# RMS.net
KiCad netlist of a schematic drawn in Altium Designer
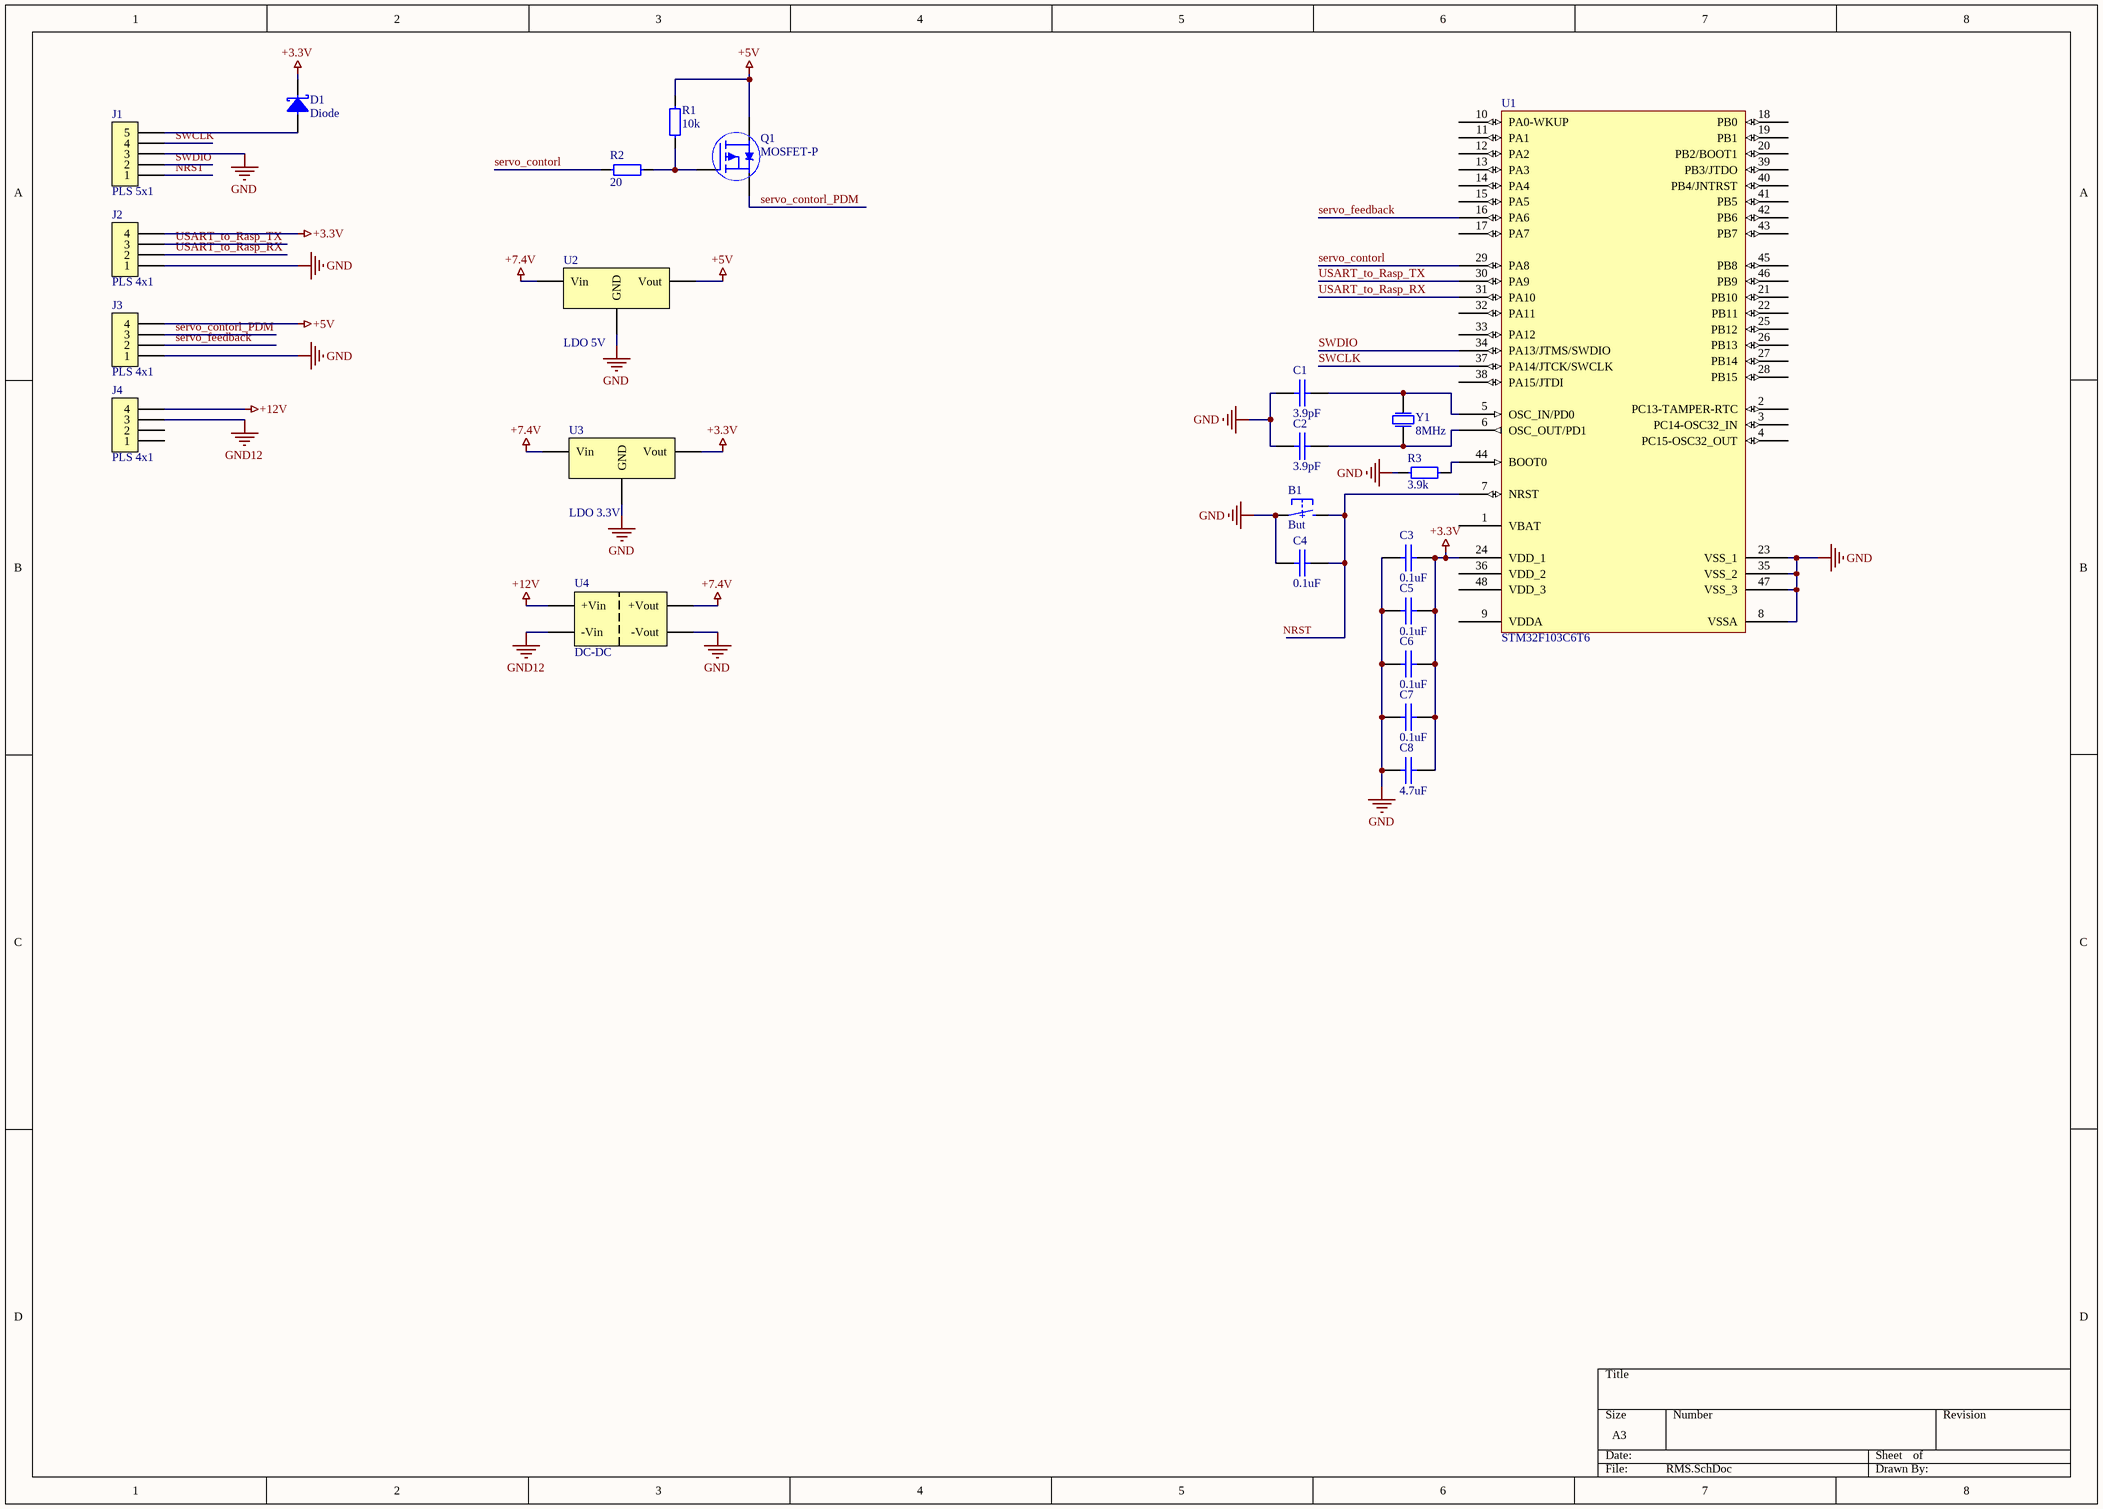
[diagram p0: RMS.SchDoc]

(export (version "E")
  (design (tool "Eeschema 10.0.6"))
  (components
    (comp (ref "B1")
      (value "But")
      (footprint "BUTTON 6x3.5")
      (description "Button 2 Conn SMD")
      (libsource (lib "RoboCor") (part "Button"))
    )
    (comp (ref "C1")
      (value "3.9pF")
      (footprint "0805 Capicator")
      (libsource (lib "RoboCor") (part "Cap 39pF"))
    )
    (comp (ref "C2")
      (value "3.9pF")
      (footprint "0805 Capicator")
      (libsource (lib "RoboCor") (part "Cap 39pF"))
    )
    (comp (ref "C3")
      (value "0.1uF")
      (footprint "0805 Capicator")
      (libsource (lib "RoboCor") (part "Cap 0.1uF"))
    )
    (comp (ref "C4")
      (value "0.1uF")
      (footprint "0805 Capicator")
      (libsource (lib "RoboCor") (part "Cap 0.1uF"))
    )
    (comp (ref "C5")
      (value "0.1uF")
      (footprint "0805 Capicator")
      (libsource (lib "RoboCor") (part "Cap 0.1uF"))
    )
    (comp (ref "C6")
      (value "0.1uF")
      (footprint "0805 Capicator")
      (libsource (lib "RoboCor") (part "Cap 0.1uF"))
    )
    (comp (ref "C7")
      (value "0.1uF")
      (footprint "0805 Capicator")
      (libsource (lib "RoboCor") (part "Cap 0.1uF"))
    )
    (comp (ref "C8")
      (value "4.7uF")
      (footprint "0805 Capicator")
      (libsource (lib "RoboCor") (part "Cap 4.7uF"))
    )
    (comp (ref "D1")
      (value "Diode")
      (footprint "sod-123")
      (description "0.5 A, Low Forward Voltage less than 385 mV, 400 mW Power Dissipation Package")
      (libsource (lib "RoboCor") (part "Diode Schottky"))
    )
    (comp (ref "J1")
      (value "PLS 5x1")
      (footprint "PLS 5x1")
      (description "Header, 5-Pin")
      (libsource (lib "RoboCor") (part "Conn 5"))
    )
    (comp (ref "J2")
      (value "PLS 4x1")
      (footprint "PLS 4x1")
      (description "Header, 4-Pin")
      (libsource (lib "RoboCor") (part "Conn 4"))
    )
    (comp (ref "J3")
      (value "PLS 4x1")
      (footprint "PLS 4x1")
      (description "Header, 4-Pin")
      (libsource (lib "RoboCor") (part "Conn 4"))
    )
    (comp (ref "J4")
      (value "PLS 4x1")
      (footprint "PLS 4x1")
      (description "Header, 4-Pin")
      (libsource (lib "RoboCor") (part "Conn 4"))
    )
    (comp (ref "Q1")
      (value "MOSFET-P")
      (footprint "SOT-23")
      (description "P-Channel Power MOSFET 12V to 20V, Infineon")
      (libsource (lib "RoboCor") (part "MOSFET-P"))
    )
    (comp (ref "R1") (value "10k") (footprint "0805 Resistor") (libsource (lib "RoboCor") (part "Res 10k")))
    (comp (ref "R2") (value "20") (footprint "0805 Resistor") (libsource (lib "RoboCor") (part "Res 20")))
    (comp (ref "R3") (value "3.9k") (footprint "0805 Resistor") (libsource (lib "RoboCor") (part "Res 3.9k")))
    (comp (ref "U1")
      (value "STM32F103C6T6")
      (footprint "STM32F103C6T6")
      (libsource (lib "RoboCor") (part "STM32F103C6T6"))
    )
    (comp (ref "U2")
      (value "LDO 5V")
      (footprint "TO-252")
      (description "LDO Regulator Pos 5V 1A")
      (libsource (lib "RoboCor") (part "LDO 5V"))
    )
    (comp (ref "U3")
      (value "LDO 3.3V")
      (footprint "SOT-223")
      (description "LDO Regulator Pos 3.3V 1.3A 4-Pin(3+Tab) SOT-223 T/R")
      (libsource (lib "RoboCor") (part "LDO 3.3V"))
    )
    (comp (ref "U4") (value "DC-DC") (footprint "DC-DC") (libsource (lib "RoboCor") (part "DC-DC")))
    (comp (ref "Y1")
      (value "8MHz")
      (footprint "hc-49sm")
      (description "Crystal. HC-49SM (US)")
      (libsource (lib "RoboCor") (part "Crystal 8MHz"))
    )
  )
  (nets
    (net (code "1") (name "+3.3V") (class "Default")
      (node (ref "C3") (pin "2") (pinfunction "2_2") (pintype "passive"))
      (node (ref "C5") (pin "2") (pinfunction "2_2") (pintype "passive"))
      (node (ref "C6") (pin "2") (pinfunction "2_2") (pintype "passive"))
      (node (ref "C7") (pin "2") (pinfunction "2_2") (pintype "passive"))
      (node (ref "C8") (pin "2") (pinfunction "2_2") (pintype "passive"))
      (node (ref "D1") (pin "2") (pinfunction "2_2") (pintype "passive"))
      (node (ref "J2") (pin "4") (pinfunction "4_4") (pintype "passive"))
      (node (ref "U1") (pin "24") (pinfunction "VDD_1_24") (pintype "power_in"))
      (node (ref "U3") (pin "2") (pinfunction "Vout_2") (pintype "power_in"))
    )
    (net (code "2") (name "+5V") (class "Default")
      (node (ref "J3") (pin "4") (pinfunction "4_4") (pintype "passive"))
      (node (ref "Q1") (pin "3") (pinfunction "Drain_3") (pintype "passive"))
      (node (ref "R1") (pin "2") (pinfunction "2_2") (pintype "passive"))
      (node (ref "U2") (pin "2") (pinfunction "Vout_2") (pintype "power_in"))
    )
    (net (code "3") (name "+7.4V") (class "Default")
      (node (ref "U2") (pin "3") (pinfunction "Vin_3") (pintype "power_in"))
      (node (ref "U3") (pin "3") (pinfunction "Vin_3") (pintype "power_in"))
      (node (ref "U4") (pin "3") (pinfunction "+Vout_3") (pintype "power_in"))
    )
    (net (code "4") (name "+12V") (class "Default")
      (node (ref "J4") (pin "4") (pinfunction "4_4") (pintype "passive"))
      (node (ref "U4") (pin "1") (pinfunction "+Vin_1") (pintype "power_in"))
    )
    (net (code "5") (name "/NRST") (class "Default")
      (node (ref "B1") (pin "2") (pinfunction "2_2") (pintype "passive"))
      (node (ref "C4") (pin "2") (pinfunction "2_2") (pintype "passive"))
      (node (ref "J1") (pin "1") (pinfunction "1_1") (pintype "passive"))
      (node (ref "U1") (pin "7") (pinfunction "NRST_7") (pintype "bidirectional"))
    )
    (net (code "6") (name "/SWCLK") (class "Default")
      (node (ref "J1") (pin "4") (pinfunction "4_4") (pintype "passive"))
      (node (ref "U1") (pin "37") (pinfunction "PA14/JTCK/SWCLK_37") (pintype "bidirectional"))
    )
    (net (code "7") (name "/SWDIO") (class "Default")
      (node (ref "J1") (pin "2") (pinfunction "2_2") (pintype "passive"))
      (node (ref "U1") (pin "34") (pinfunction "PA13/JTMS/SWDIO_34") (pintype "bidirectional"))
    )
    (net (code "8") (name "/USART_to_Rasp_RX") (class "Default")
      (node (ref "J2") (pin "2") (pinfunction "2_2") (pintype "passive"))
      (node (ref "U1") (pin "31") (pinfunction "PA10_31") (pintype "bidirectional"))
    )
    (net (code "9") (name "/USART_to_Rasp_TX") (class "Default")
      (node (ref "J2") (pin "3") (pinfunction "3_3") (pintype "passive"))
      (node (ref "U1") (pin "30") (pinfunction "PA9_30") (pintype "bidirectional"))
    )
    (net (code "10") (name "/servo_contorl") (class "Default")
      (node (ref "R2") (pin "1") (pinfunction "1_1") (pintype "passive"))
      (node (ref "U1") (pin "29") (pinfunction "PA8_29") (pintype "bidirectional"))
    )
    (net (code "11") (name "/servo_contorl_PDM") (class "Default")
      (node (ref "J3") (pin "3") (pinfunction "3_3") (pintype "passive"))
      (node (ref "Q1") (pin "2") (pinfunction "Source_2") (pintype "passive"))
    )
    (net (code "12") (name "/servo_feedback") (class "Default")
      (node (ref "J3") (pin "2") (pinfunction "2_2") (pintype "passive"))
      (node (ref "U1") (pin "16") (pinfunction "PA6_16") (pintype "bidirectional"))
    )
    (net (code "13") (name "GND") (class "Default")
      (node (ref "B1") (pin "1") (pinfunction "1_1") (pintype "passive"))
      (node (ref "C1") (pin "1") (pinfunction "1_1") (pintype "passive"))
      (node (ref "C2") (pin "1") (pinfunction "1_1") (pintype "passive"))
      (node (ref "C3") (pin "1") (pinfunction "1_1") (pintype "passive"))
      (node (ref "C4") (pin "1") (pinfunction "1_1") (pintype "passive"))
      (node (ref "C5") (pin "1") (pinfunction "1_1") (pintype "passive"))
      (node (ref "C6") (pin "1") (pinfunction "1_1") (pintype "passive"))
      (node (ref "C7") (pin "1") (pinfunction "1_1") (pintype "passive"))
      (node (ref "C8") (pin "1") (pinfunction "1_1") (pintype "passive"))
      (node (ref "J1") (pin "3") (pinfunction "3_3") (pintype "passive"))
      (node (ref "J2") (pin "1") (pinfunction "1_1") (pintype "passive"))
      (node (ref "J3") (pin "1") (pinfunction "1_1") (pintype "passive"))
      (node (ref "R3") (pin "1") (pinfunction "1_1") (pintype "passive"))
      (node (ref "U1") (pin "23") (pinfunction "VSS_1_23") (pintype "power_in"))
      (node (ref "U1") (pin "35") (pinfunction "VSS_2_35") (pintype "power_in"))
      (node (ref "U1") (pin "47") (pinfunction "VSS_3_47") (pintype "power_in"))
      (node (ref "U1") (pin "8") (pinfunction "VSSA_8") (pintype "power_in"))
      (node (ref "U2") (pin "1") (pinfunction "GND_1") (pintype "power_in"))
      (node (ref "U3") (pin "1") (pinfunction "GND_1") (pintype "power_in"))
      (node (ref "U4") (pin "4") (pinfunction "-Vout_4") (pintype "power_in"))
    )
    (net (code "14") (name "GND12") (class "Default")
      (node (ref "J4") (pin "3") (pinfunction "3_3") (pintype "passive"))
      (node (ref "U4") (pin "2") (pinfunction "-Vin_2") (pintype "power_in"))
    )
    (net (code "15") (name "Net-(D1-Pad1)") (class "Default")
      (node (ref "D1") (pin "1") (pinfunction "1_1") (pintype "passive"))
      (node (ref "J1") (pin "5") (pinfunction "5_5") (pintype "passive"))
    )
    (net (code "16") (name "Net-(Q1-Gate)") (class "Default")
      (node (ref "Q1") (pin "1") (pinfunction "Gate_1") (pintype "passive"))
      (node (ref "R1") (pin "1") (pinfunction "1_1") (pintype "passive"))
      (node (ref "R2") (pin "2") (pinfunction "2_2") (pintype "passive"))
    )
    (net (code "17") (name "Net-(U1-BOOT0)") (class "Default")
      (node (ref "R3") (pin "2") (pinfunction "2_2") (pintype "passive"))
      (node (ref "U1") (pin "44") (pinfunction "BOOT0_44") (pintype "input"))
    )
    (net (code "18") (name "Net-(U1-OSC_IN{slash}PD0)") (class "Default")
      (node (ref "C1") (pin "2") (pinfunction "2_2") (pintype "passive"))
      (node (ref "U1") (pin "5") (pinfunction "OSC_IN/PD0_5") (pintype "input"))
      (node (ref "Y1") (pin "2") (pinfunction "2_2") (pintype "passive"))
    )
    (net (code "19") (name "Net-(U1-OSC_OUT{slash}PD1)") (class "Default")
      (node (ref "C2") (pin "2") (pinfunction "2_2") (pintype "passive"))
      (node (ref "U1") (pin "6") (pinfunction "OSC_OUT/PD1_6") (pintype "output"))
      (node (ref "Y1") (pin "1") (pinfunction "1_1") (pintype "passive"))
    )
    (net (code "20") (name "unconnected-(J4-Pad1)") (class "Default")
      (node (ref "J4") (pin "1") (pinfunction "1_1") (pintype "passive"))
    )
    (net (code "21") (name "unconnected-(J4-Pad2)") (class "Default")
      (node (ref "J4") (pin "2") (pinfunction "2_2") (pintype "passive"))
    )
    (net (code "22") (name "unconnected-(U1-PA0-WKUP-Pad10)") (class "Default")
      (node (ref "U1") (pin "10") (pinfunction "PA0-WKUP_10") (pintype "bidirectional"))
    )
    (net (code "23") (name "unconnected-(U1-PA1-Pad11)") (class "Default")
      (node (ref "U1") (pin "11") (pinfunction "PA1_11") (pintype "bidirectional"))
    )
    (net (code "24") (name "unconnected-(U1-PA2-Pad12)") (class "Default")
      (node (ref "U1") (pin "12") (pinfunction "PA2_12") (pintype "bidirectional"))
    )
    (net (code "25") (name "unconnected-(U1-PA3-Pad13)") (class "Default")
      (node (ref "U1") (pin "13") (pinfunction "PA3_13") (pintype "bidirectional"))
    )
    (net (code "26") (name "unconnected-(U1-PA4-Pad14)") (class "Default")
      (node (ref "U1") (pin "14") (pinfunction "PA4_14") (pintype "bidirectional"))
    )
    (net (code "27") (name "unconnected-(U1-PA5-Pad15)") (class "Default")
      (node (ref "U1") (pin "15") (pinfunction "PA5_15") (pintype "bidirectional"))
    )
    (net (code "28") (name "unconnected-(U1-PA7-Pad17)") (class "Default")
      (node (ref "U1") (pin "17") (pinfunction "PA7_17") (pintype "bidirectional"))
    )
    (net (code "29") (name "unconnected-(U1-PA11-Pad32)") (class "Default")
      (node (ref "U1") (pin "32") (pinfunction "PA11_32") (pintype "bidirectional"))
    )
    (net (code "30") (name "unconnected-(U1-PA12-Pad33)") (class "Default")
      (node (ref "U1") (pin "33") (pinfunction "PA12_33") (pintype "bidirectional"))
    )
    (net (code "31") (name "unconnected-(U1-PA15{slash}JTDI-Pad38)") (class "Default")
      (node (ref "U1") (pin "38") (pinfunction "PA15/JTDI_38") (pintype "bidirectional"))
    )
    (net (code "32") (name "unconnected-(U1-PB0-Pad18)") (class "Default")
      (node (ref "U1") (pin "18") (pinfunction "PB0_18") (pintype "bidirectional"))
    )
    (net (code "33") (name "unconnected-(U1-PB1-Pad19)") (class "Default")
      (node (ref "U1") (pin "19") (pinfunction "PB1_19") (pintype "bidirectional"))
    )
    (net (code "34") (name "unconnected-(U1-PB2{slash}BOOT1-Pad20)") (class "Default")
      (node (ref "U1") (pin "20") (pinfunction "PB2/BOOT1_20") (pintype "bidirectional"))
    )
    (net (code "35") (name "unconnected-(U1-PB3{slash}JTDO-Pad39)") (class "Default")
      (node (ref "U1") (pin "39") (pinfunction "PB3/JTDO_39") (pintype "bidirectional"))
    )
    (net (code "36") (name "unconnected-(U1-PB4{slash}JNTRST-Pad40)") (class "Default")
      (node (ref "U1") (pin "40") (pinfunction "PB4/JNTRST_40") (pintype "bidirectional"))
    )
    (net (code "37") (name "unconnected-(U1-PB5-Pad41)") (class "Default")
      (node (ref "U1") (pin "41") (pinfunction "PB5_41") (pintype "bidirectional"))
    )
    (net (code "38") (name "unconnected-(U1-PB6-Pad42)") (class "Default")
      (node (ref "U1") (pin "42") (pinfunction "PB6_42") (pintype "bidirectional"))
    )
    (net (code "39") (name "unconnected-(U1-PB7-Pad43)") (class "Default")
      (node (ref "U1") (pin "43") (pinfunction "PB7_43") (pintype "bidirectional"))
    )
    (net (code "40") (name "unconnected-(U1-PB8-Pad45)") (class "Default")
      (node (ref "U1") (pin "45") (pinfunction "PB8_45") (pintype "bidirectional"))
    )
    (net (code "41") (name "unconnected-(U1-PB9-Pad46)") (class "Default")
      (node (ref "U1") (pin "46") (pinfunction "PB9_46") (pintype "bidirectional"))
    )
    (net (code "42") (name "unconnected-(U1-PB10-Pad21)") (class "Default")
      (node (ref "U1") (pin "21") (pinfunction "PB10_21") (pintype "bidirectional"))
    )
    (net (code "43") (name "unconnected-(U1-PB11-Pad22)") (class "Default")
      (node (ref "U1") (pin "22") (pinfunction "PB11_22") (pintype "bidirectional"))
    )
    (net (code "44") (name "unconnected-(U1-PB12-Pad25)") (class "Default")
      (node (ref "U1") (pin "25") (pinfunction "PB12_25") (pintype "bidirectional"))
    )
    (net (code "45") (name "unconnected-(U1-PB13-Pad26)") (class "Default")
      (node (ref "U1") (pin "26") (pinfunction "PB13_26") (pintype "bidirectional"))
    )
    (net (code "46") (name "unconnected-(U1-PB14-Pad27)") (class "Default")
      (node (ref "U1") (pin "27") (pinfunction "PB14_27") (pintype "bidirectional"))
    )
    (net (code "47") (name "unconnected-(U1-PB15-Pad28)") (class "Default")
      (node (ref "U1") (pin "28") (pinfunction "PB15_28") (pintype "bidirectional"))
    )
    (net (code "48") (name "unconnected-(U1-PC13-TAMPER-RTC-Pad2)") (class "Default")
      (node (ref "U1") (pin "2") (pinfunction "PC13-TAMPER-RTC_2") (pintype "bidirectional"))
    )
    (net (code "49") (name "unconnected-(U1-PC14-OSC32_IN-Pad3)") (class "Default")
      (node (ref "U1") (pin "3") (pinfunction "PC14-OSC32_IN_3") (pintype "bidirectional"))
    )
    (net (code "50") (name "unconnected-(U1-PC15-OSC32_OUT-Pad4)") (class "Default")
      (node (ref "U1") (pin "4") (pinfunction "PC15-OSC32_OUT_4") (pintype "bidirectional"))
    )
    (net (code "51") (name "unconnected-(U1-VBAT-Pad1)") (class "Default")
      (node (ref "U1") (pin "1") (pinfunction "VBAT_1") (pintype "power_in"))
    )
    (net (code "52") (name "unconnected-(U1-VDDA-Pad9)") (class "Default")
      (node (ref "U1") (pin "9") (pinfunction "VDDA_9") (pintype "power_in"))
    )
    (net (code "53") (name "unconnected-(U1-VDD_2-Pad36)") (class "Default")
      (node (ref "U1") (pin "36") (pinfunction "VDD_2_36") (pintype "power_in"))
    )
    (net (code "54") (name "unconnected-(U1-VDD_3-Pad48)") (class "Default")
      (node (ref "U1") (pin "48") (pinfunction "VDD_3_48") (pintype "power_in"))
    )
  )
)
